# Sheet1.net
KiCad netlist of a schematic drawn in Altium Designer
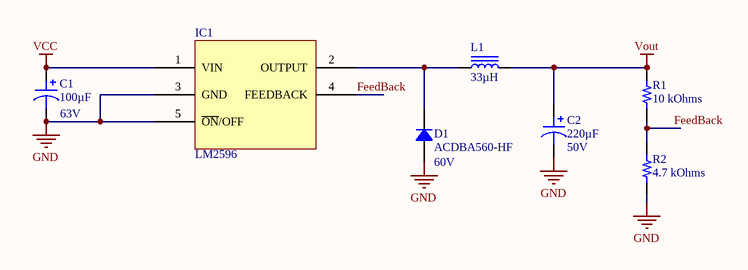
[diagram p0: Sheet1.SchDoc]

(export (version "E")
  (design (tool "Eeschema 10.0.6"))
  (components
    (comp (ref "C1")
      (value "100µF")
      (footprint "CAP TH ALUM ELEC D8.00mm S3.50mm H12.50mm")
      (description "CAP ALUM 100UF 20% 63V RADIAL")
      (fields
        (field (name "PART NUMBER") "ECA-1JM101")
        (field (name "MANUFACTURER") "Panasonic Electronic Components")
        (field (name "VOLTAGE - RATED") "63V")
      )
      (libsource (lib "Celestial Altium Library - altium_library") (part "Polarised Capacitor"))
    )
    (comp (ref "C2")
      (value "220µF")
      (footprint "CAP TH ALUM ELEC D10.00mm S5.00mm H13.50mm")
      (description "CAP ALUM 220UF 20% 50V RADIAL")
      (fields
        (field (name "PART NUMBER") "ECA-1HM221")
        (field (name "MANUFACTURER") "Panasonic Electronic Components")
        (field (name "VOLTAGE - RATED") "50V")
      )
      (libsource (lib "Celestial Altium Library - altium_library") (part "Polarised Capacitor"))
    )
    (comp (ref "D1")
      (value "ACDBA560-HF")
      (footprint "DO214AC SMA")
      (description "DIODE SCHOTTKY 60V 5A DO214AC")
      (fields
        (field (name "MANUFACTURER") "Comchip Technology")
        (field (name "VOLTAGE - DC REVERSE (VR) (MAX)") "60V")
      )
      (libsource (lib "Celestial Altium Library - altium_library") (part "Diode"))
    )
    (comp (ref "IC1") (value "LM2596") (footprint "D2PAC") (libsource (lib "Schlib1") (part "LM2596")))
    (comp (ref "L1")
      (value "33µH")
      (footprint "BOURNS SRR1280")
      (description "FIXED IND 33UH 3.5A 57 MOHM SMD")
      (fields (field (name "PART NUMBER") "SRR1280-330M") (field (name "MANUFACTURER") "Bourns Inc."))
      (libsource (lib "Celestial Altium Library - altium_library") (part "Inductor"))
    )
    (comp (ref "R1")
      (value "10 kOhms")
      (footprint "RES 0805_2012")
      (description "RES 10K OHM 1% 1/4W 0805")
      (fields
        (field (name "PART NUMBER") "RNCP0805FTD10K0")
        (field (name "MANUFACTURER") "Stackpole Electronics Inc")
      )
      (libsource (lib "Celestial Altium Library - altium_library") (part "Resistor"))
    )
    (comp (ref "R2")
      (value "4.7 kOhms")
      (footprint "RES 0805_2012")
      (description "CRGP 0805 4K7 1%")
      (fields
        (field (name "PART NUMBER") "CRGP0805F4K7")
        (field (name "MANUFACTURER") "TE Connectivity Passive Product")
      )
      (libsource (lib "Celestial Altium Library - altium_library") (part "Resistor"))
    )
  )
  (nets
    (net (code "1") (name "/FeedBack") (class "Default")
      (node (ref "IC1") (pin "4") (pinfunction "FEEDBACK_4") (pintype "passive"))
      (node (ref "R1") (pin "1") (pinfunction "1_1") (pintype "passive"))
      (node (ref "R2") (pin "2") (pinfunction "2_2") (pintype "passive"))
    )
    (net (code "2") (name "GND") (class "Default")
      (node (ref "C1") (pin "2") (pinfunction "2_2") (pintype "passive"))
      (node (ref "C2") (pin "2") (pinfunction "2_2") (pintype "passive"))
      (node (ref "D1") (pin "1") (pinfunction "1_1") (pintype "passive"))
      (node (ref "IC1") (pin "3") (pinfunction "GND_3") (pintype "passive"))
      (node (ref "IC1") (pin "5") (pinfunction "~{ON}/OFF_5") (pintype "passive"))
      (node (ref "R2") (pin "1") (pinfunction "1_1") (pintype "passive"))
    )
    (net (code "3") (name "Net-(IC1-OUTPUT)") (class "Default")
      (node (ref "D1") (pin "2") (pinfunction "2_2") (pintype "passive"))
      (node (ref "IC1") (pin "2") (pinfunction "OUTPUT_2") (pintype "passive"))
      (node (ref "L1") (pin "1") (pinfunction "1_1") (pintype "passive"))
    )
    (net (code "4") (name "VCC") (class "Default")
      (node (ref "C1") (pin "1") (pinfunction "1_1") (pintype "passive"))
      (node (ref "IC1") (pin "1") (pinfunction "VIN_1") (pintype "passive"))
    )
    (net (code "5") (name "Vout") (class "Default")
      (node (ref "C2") (pin "1") (pinfunction "1_1") (pintype "passive"))
      (node (ref "L1") (pin "2") (pinfunction "2_2") (pintype "passive"))
      (node (ref "R1") (pin "2") (pinfunction "2_2") (pintype "passive"))
    )
  )
)
